# controller.net
KiCad netlist of a schematic drawn in Altium Designer
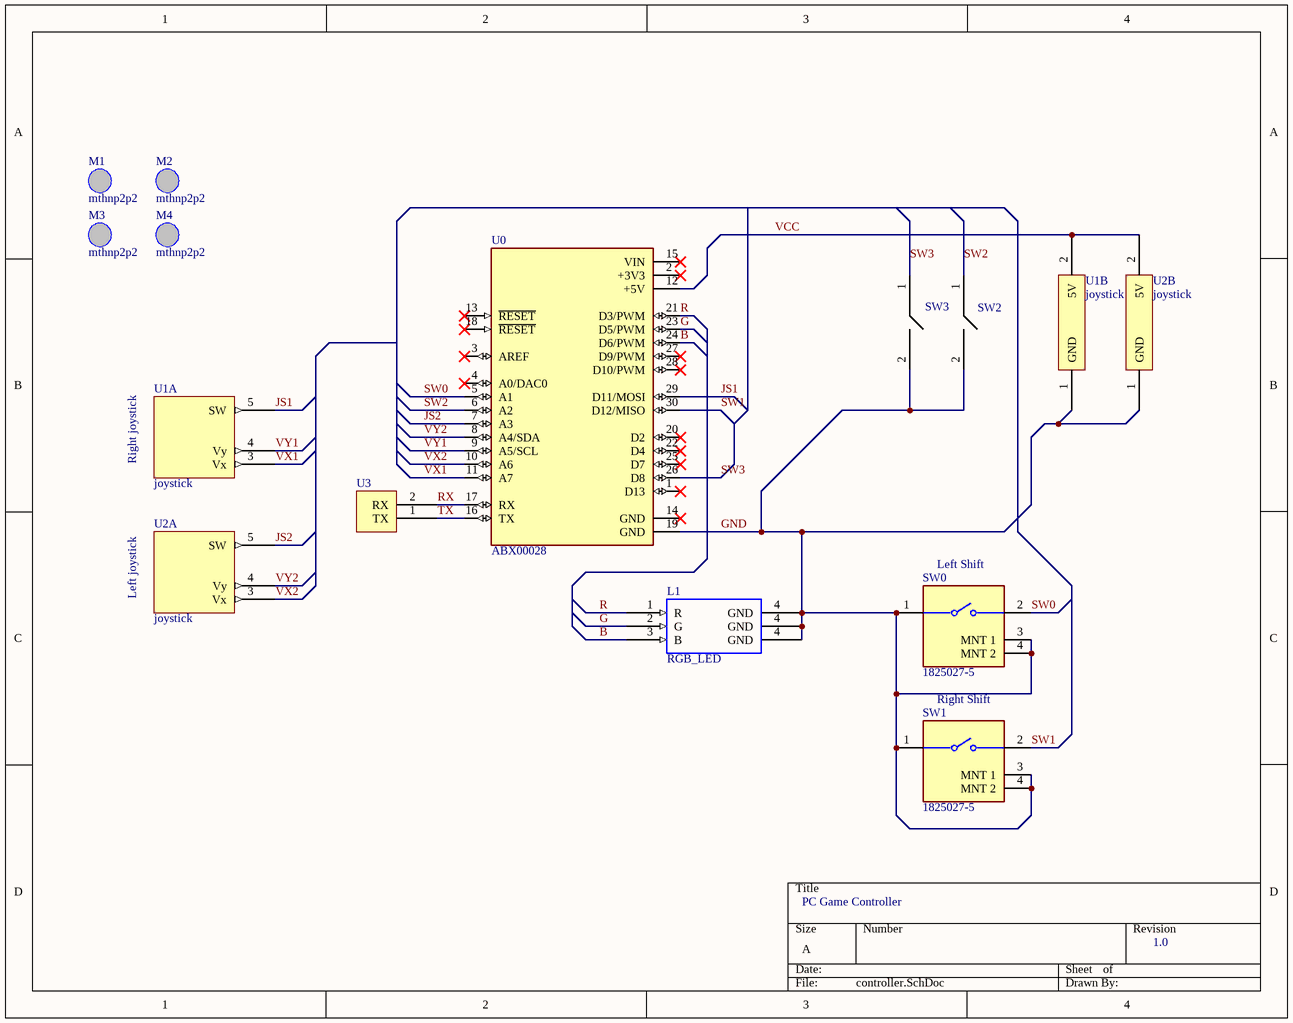
[diagram p0: controller.SchDoc]

(export (version "E")
  (design (tool "Eeschema 10.0.6"))
  (components
    (comp (ref "L1") (value "RGB_LED") (footprint "RGB_LED") (libsource (lib "RGB_LED") (part "RGB_LED")))
    (comp (ref "M1") (value "mthnp2p2") (footprint "mthnp2p2") (libsource (lib "mthnp2p2") (part "mthnp2p2")))
    (comp (ref "M2") (value "mthnp2p2") (footprint "mthnp2p2") (libsource (lib "mthnp2p2") (part "mthnp2p2")))
    (comp (ref "M3") (value "mthnp2p2") (footprint "mthnp2p2") (libsource (lib "mthnp2p2") (part "mthnp2p2")))
    (comp (ref "M4") (value "mthnp2p2") (footprint "mthnp2p2") (libsource (lib "mthnp2p2") (part "mthnp2p2")))
    (comp (ref "SW0")
      (value "1825027-5")
      (footprint "FP-1825027-5-0")
      (description "SWITCH TACTILE SPST-NO 0.05A 24V")
      (fields
        (field (name "MANUFACTURER") "TE Connectivity")
        (field (name "OCTOPART") "https://octopart.com/1825027-5-te+connectivity-46510878")
      )
      (libsource (lib "Altium Content Vault") (part "338960e5b609f119bcfc96db856e8f7"))
    )
    (comp (ref "SW1")
      (value "1825027-5")
      (footprint "FP-1825027-5-0")
      (description "SWITCH TACTILE SPST-NO 0.05A 24V")
      (fields
        (field (name "MANUFACTURER") "TE Connectivity")
        (field (name "OCTOPART") "https://octopart.com/1825027-5-te+connectivity-46510878")
      )
      (libsource (lib "Altium Content Vault") (part "338960e5b609f119bcfc96db856e8f7"))
    )
    (comp (ref "SW2") (value "~") (footprint "DIP_BUTTON") (libsource (lib "button") (part "button")))
    (comp (ref "SW3") (value "~") (footprint "DIP_BUTTON") (libsource (lib "button") (part "button")))
    (comp (ref "U0")
      (value "ABX00028")
      (footprint "MODULE_ABX00028")
      (description "Arduinoâ€™s 5V compatible board in the smallest available form factor: 45x18mm!")
      (fields (field (name "MP") "Arduino Nano Every") (field (name "MF") "Arduino"))
      (libsource (lib "ABX00028") (part "ABX00028"))
    )
    (comp (ref "U1") (value "joystick") (footprint "joystick") (libsource (lib "joystick") (part "joystick")))
    (comp (ref "U2") (value "joystick") (footprint "joystick") (libsource (lib "joystick") (part "joystick")))
    (comp (ref "U3") (value "~") (footprint "PCBComponent_1") (libsource (lib "uart_connector") (part "U*")))
  )
  (nets
    (net (code "1") (name "/B") (class "Default")
      (node (ref "L1") (pin "3") (pinfunction "B_3") (pintype "input"))
      (node (ref "U0") (pin "24") (pinfunction "D6/PWM_24") (pintype "bidirectional"))
    )
    (net (code "2") (name "/G") (class "Default")
      (node (ref "L1") (pin "2") (pinfunction "G_2") (pintype "input"))
      (node (ref "U0") (pin "23") (pinfunction "D5/PWM_23") (pintype "bidirectional"))
    )
    (net (code "3") (name "/GND") (class "Default")
      (node (ref "L1") (pin "4") (pinfunction "GND_4") (pintype "power_in"))
      (node (ref "SW0") (pin "1") (pinfunction "1_1") (pintype "passive"))
      (node (ref "SW0") (pin "3") (pinfunction "MNT_1_3") (pintype "passive"))
      (node (ref "SW0") (pin "4") (pinfunction "MNT_2_4") (pintype "passive"))
      (node (ref "SW1") (pin "1") (pinfunction "1_1") (pintype "passive"))
      (node (ref "SW1") (pin "3") (pinfunction "MNT_1_3") (pintype "passive"))
      (node (ref "SW1") (pin "4") (pinfunction "MNT_2_4") (pintype "passive"))
      (node (ref "SW2") (pin "2") (pintype "passive"))
      (node (ref "SW3") (pin "2") (pintype "passive"))
      (node (ref "U0") (pin "19") (pinfunction "GND_19") (pintype "power_in"))
      (node (ref "U1") (pin "1") (pinfunction "GND_1") (pintype "power_in"))
      (node (ref "U2") (pin "1") (pinfunction "GND_1") (pintype "power_in"))
    )
    (net (code "4") (name "/JS1") (class "Default")
      (node (ref "U0") (pin "29") (pinfunction "D11/MOSI_29") (pintype "bidirectional"))
      (node (ref "U1") (pin "5") (pinfunction "SW_5") (pintype "output"))
    )
    (net (code "5") (name "/JS2") (class "Default")
      (node (ref "U0") (pin "7") (pinfunction "A3_7") (pintype "bidirectional"))
      (node (ref "U2") (pin "5") (pinfunction "SW_5") (pintype "output"))
    )
    (net (code "6") (name "/R") (class "Default")
      (node (ref "L1") (pin "1") (pinfunction "R_1") (pintype "input"))
      (node (ref "U0") (pin "21") (pinfunction "D3/PWM_21") (pintype "bidirectional"))
    )
    (net (code "7") (name "/RX") (class "Default")
      (node (ref "U0") (pin "17") (pinfunction "RX_17") (pintype "bidirectional"))
      (node (ref "U3") (pin "2") (pinfunction "RX_2") (pintype "passive"))
    )
    (net (code "8") (name "/SW0") (class "Default")
      (node (ref "SW0") (pin "2") (pinfunction "2_2") (pintype "passive"))
      (node (ref "U0") (pin "5") (pinfunction "A1_5") (pintype "bidirectional"))
    )
    (net (code "9") (name "/SW1") (class "Default")
      (node (ref "SW1") (pin "2") (pinfunction "2_2") (pintype "passive"))
      (node (ref "U0") (pin "30") (pinfunction "D12/MISO_30") (pintype "bidirectional"))
    )
    (net (code "10") (name "/SW2") (class "Default")
      (node (ref "SW2") (pin "1") (pintype "passive"))
      (node (ref "U0") (pin "6") (pinfunction "A2_6") (pintype "bidirectional"))
    )
    (net (code "11") (name "/SW3") (class "Default")
      (node (ref "SW3") (pin "1") (pintype "passive"))
      (node (ref "U0") (pin "26") (pinfunction "D8_26") (pintype "bidirectional"))
    )
    (net (code "12") (name "/TX") (class "Default")
      (node (ref "U0") (pin "16") (pinfunction "TX_16") (pintype "bidirectional"))
      (node (ref "U3") (pin "1") (pinfunction "TX_1") (pintype "passive"))
    )
    (net (code "13") (name "/VCC") (class "Default")
      (node (ref "U0") (pin "12") (pinfunction "+5V_12") (pintype "power_in"))
      (node (ref "U1") (pin "2") (pinfunction "5V_2") (pintype "power_in"))
      (node (ref "U2") (pin "2") (pinfunction "5V_2") (pintype "power_in"))
    )
    (net (code "14") (name "/VX1") (class "Default")
      (node (ref "U0") (pin "11") (pinfunction "A7_11") (pintype "bidirectional"))
      (node (ref "U1") (pin "3") (pinfunction "Vx_3") (pintype "output"))
    )
    (net (code "15") (name "/VX2") (class "Default")
      (node (ref "U0") (pin "10") (pinfunction "A6_10") (pintype "bidirectional"))
      (node (ref "U2") (pin "3") (pinfunction "Vx_3") (pintype "output"))
    )
    (net (code "16") (name "/VY1") (class "Default")
      (node (ref "U0") (pin "9") (pinfunction "A5/SCL_9") (pintype "bidirectional"))
      (node (ref "U1") (pin "4") (pinfunction "Vy_4") (pintype "output"))
    )
    (net (code "17") (name "/VY2") (class "Default")
      (node (ref "U0") (pin "8") (pinfunction "A4/SDA_8") (pintype "bidirectional"))
      (node (ref "U2") (pin "4") (pinfunction "Vy_4") (pintype "output"))
    )
    (net (code "18") (name "unconnected-(U0-+3V3-Pad2)") (class "Default")
      (node (ref "U0") (pin "2") (pinfunction "+3V3_2") (pintype "power_in+no_connect"))
    )
    (net (code "19") (name "unconnected-(U0-A0{slash}DAC0-Pad4)") (class "Default")
      (node (ref "U0") (pin "4") (pinfunction "A0/DAC0_4") (pintype "bidirectional+no_connect"))
    )
    (net (code "20") (name "unconnected-(U0-AREF-Pad3)") (class "Default")
      (node (ref "U0") (pin "3") (pinfunction "AREF_3") (pintype "bidirectional+no_connect"))
    )
    (net (code "21") (name "unconnected-(U0-D2-Pad20)") (class "Default")
      (node (ref "U0") (pin "20") (pinfunction "D2_20") (pintype "bidirectional+no_connect"))
    )
    (net (code "22") (name "unconnected-(U0-D4-Pad22)") (class "Default")
      (node (ref "U0") (pin "22") (pinfunction "D4_22") (pintype "bidirectional+no_connect"))
    )
    (net (code "23") (name "unconnected-(U0-D7-Pad25)") (class "Default")
      (node (ref "U0") (pin "25") (pinfunction "D7_25") (pintype "bidirectional+no_connect"))
    )
    (net (code "24") (name "unconnected-(U0-D9{slash}PWM-Pad27)") (class "Default")
      (node (ref "U0") (pin "27") (pinfunction "D9/PWM_27") (pintype "bidirectional+no_connect"))
    )
    (net (code "25") (name "unconnected-(U0-D10{slash}PWM-Pad28)") (class "Default")
      (node (ref "U0") (pin "28") (pinfunction "D10/PWM_28") (pintype "bidirectional+no_connect"))
    )
    (net (code "26") (name "unconnected-(U0-D13-Pad1)") (class "Default")
      (node (ref "U0") (pin "1") (pinfunction "D13_1") (pintype "bidirectional+no_connect"))
    )
    (net (code "27") (name "unconnected-(U0-GND-Pad14)") (class "Default")
      (node (ref "U0") (pin "14") (pinfunction "GND_14") (pintype "power_in+no_connect"))
    )
    (net (code "28") (name "unconnected-(U0-VIN-Pad15)") (class "Default")
      (node (ref "U0") (pin "15") (pinfunction "VIN_15") (pintype "power_in+no_connect"))
    )
    (net (code "29") (name "unconnected-(U0-~{RESET}-Pad13)") (class "Default")
      (node (ref "U0") (pin "13") (pinfunction "~{RESET}_13") (pintype "input+no_connect"))
    )
    (net (code "30") (name "unconnected-(U0-~{RESET}-Pad18)") (class "Default")
      (node (ref "U0") (pin "18") (pinfunction "~{RESET}_18") (pintype "input+no_connect"))
    )
  )
)
